# MCU.net
KiCad netlist of a schematic drawn in Altium Designer
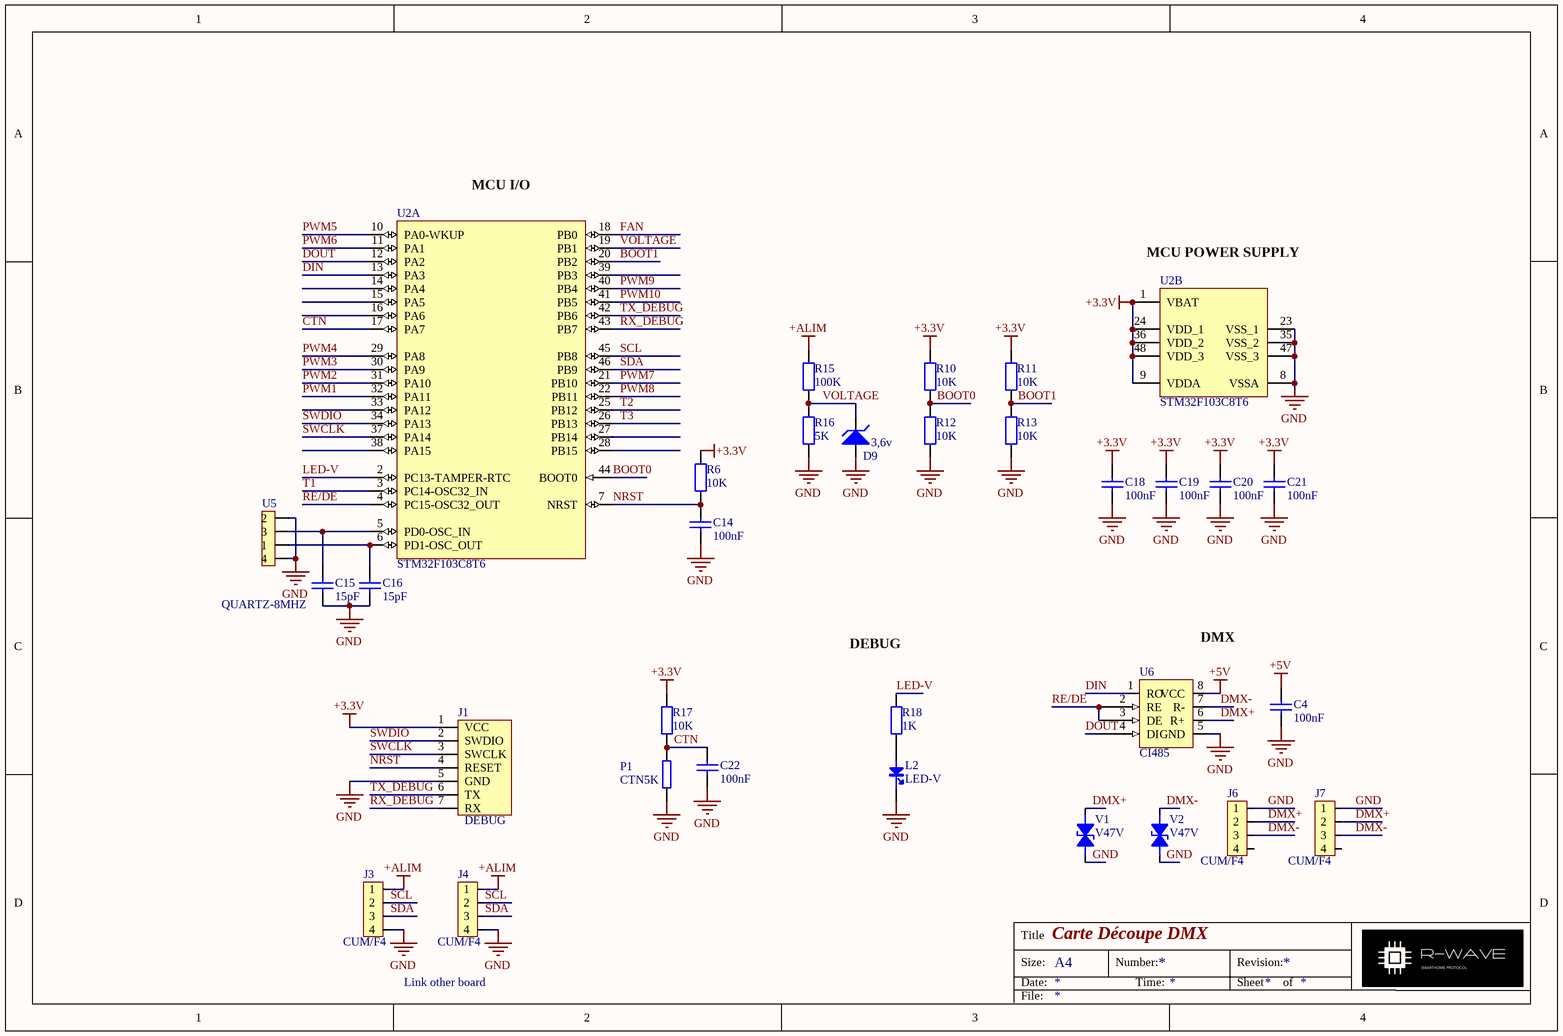
[diagram p0: MCU.SchDoc]

(export (version "E")
  (design (tool "Eeschema 10.0.6"))
  (components
    (comp (ref "C4")
      (value "100nF")
      (footprint "C0603")
      (description "Capacitor")
      (libsource (lib "MyLibrary") (part "Cap"))
    )
    (comp (ref "C14")
      (value "100nF")
      (footprint "C0603")
      (description "Capacitor")
      (libsource (lib "MyLibrary") (part "Cap"))
    )
    (comp (ref "C15")
      (value "15pF")
      (footprint "C0603")
      (description "Capacitor")
      (libsource (lib "MyLibrary") (part "Cap"))
    )
    (comp (ref "C16")
      (value "15pF")
      (footprint "C0603")
      (description "Capacitor")
      (libsource (lib "MyLibrary") (part "Cap"))
    )
    (comp (ref "C18")
      (value "100nF")
      (footprint "C0603")
      (description "Capacitor")
      (libsource (lib "MyLibrary") (part "Cap"))
    )
    (comp (ref "C19")
      (value "100nF")
      (footprint "C0603")
      (description "Capacitor")
      (libsource (lib "MyLibrary") (part "Cap"))
    )
    (comp (ref "C20")
      (value "100nF")
      (footprint "C0603")
      (description "Capacitor")
      (libsource (lib "MyLibrary") (part "Cap"))
    )
    (comp (ref "C21")
      (value "100nF")
      (footprint "C0603")
      (description "Capacitor")
      (libsource (lib "MyLibrary") (part "Cap"))
    )
    (comp (ref "C22")
      (value "100nF")
      (footprint "C0603")
      (description "Capacitor")
      (libsource (lib "MyLibrary") (part "Cap"))
    )
    (comp (ref "D9")
      (value "3,6v")
      (footprint "SOD123")
      (description "Zener Diode")
      (libsource (lib "MyLibrary") (part "D Zener"))
    )
    (comp (ref "J1")
      (value "~")
      (footprint "CON_PROG")
      (description "Programming Connector")
      (libsource (lib "MyLibrary") (part "CON-PROG"))
    )
    (comp (ref "J3")
      (value "CUM/F4")
      (footprint "CNT4F5")
      (description "connecteur  4 points")
      (libsource (lib "PROTEL") (part "CUM/F4"))
    )
    (comp (ref "J4")
      (value "CUM/F4")
      (footprint "CNT4F5")
      (description "connecteur  4 points")
      (libsource (lib "PROTEL") (part "CUM/F4"))
    )
    (comp (ref "J6")
      (value "CUM/F4")
      (footprint "CNT4S")
      (description "connecteur  4 points")
      (libsource (lib "PROTEL") (part "CUM/F4"))
    )
    (comp (ref "J7")
      (value "CUM/F4")
      (footprint "CNT4S")
      (description "connecteur  4 points")
      (libsource (lib "PROTEL") (part "CUM/F4"))
    )
    (comp (ref "L2")
      (value "LED-V")
      (footprint "LED-V1A")
      (description "LED  piquer  ou  CMS verte")
      (libsource (lib "PROTEL") (part "LED-V"))
    )
    (comp (ref "P1")
      (value "CTN5K")
      (footprint "DIV015")
      (description "Photoresistance")
      (libsource (lib "PROTEL") (part "CTN5K"))
    )
    (comp (ref "R6")
      (value "10K")
      (footprint "R0603")
      (description "Thin Metal Film Resistor")
      (libsource (lib "MyLibrary") (part "Res"))
    )
    (comp (ref "R10")
      (value "10K")
      (footprint "R0603")
      (description "Thin Metal Film Resistor")
      (libsource (lib "MyLibrary") (part "Res"))
    )
    (comp (ref "R11")
      (value "10K")
      (footprint "R0603")
      (description "Thin Metal Film Resistor")
      (libsource (lib "MyLibrary") (part "Res"))
    )
    (comp (ref "R12")
      (value "10K")
      (footprint "R0603")
      (description "Thin Metal Film Resistor")
      (libsource (lib "MyLibrary") (part "Res"))
    )
    (comp (ref "R13")
      (value "10K")
      (footprint "R0603")
      (description "Thin Metal Film Resistor")
      (libsource (lib "MyLibrary") (part "Res"))
    )
    (comp (ref "R15")
      (value "100K")
      (footprint "R0603")
      (description "Thin Metal Film Resistor")
      (libsource (lib "MyLibrary") (part "Res"))
    )
    (comp (ref "R16")
      (value "5K")
      (footprint "R0603")
      (description "Thin Metal Film Resistor")
      (libsource (lib "MyLibrary") (part "Res"))
    )
    (comp (ref "R17")
      (value "10K")
      (footprint "R0603")
      (description "Thin Metal Film Resistor")
      (libsource (lib "MyLibrary") (part "Res"))
    )
    (comp (ref "R18")
      (value "1K")
      (footprint "R0603")
      (description "Thin Metal Film Resistor")
      (libsource (lib "MyLibrary") (part "Res"))
    )
    (comp (ref "U2")
      (value "STM32F103C8T6")
      (footprint "TQFP-48")
      (libsource (lib "MyLibrary") (part "STM32F103C8T6"))
    )
    (comp (ref "U5")
      (value "QUARTZ-8MHZ")
      (footprint "QUA8G")
      (description "QUARTZ 8 MHZ CMS")
      (libsource (lib "PROTEL") (part "QUARTZ-8MHZ"))
    )
    (comp (ref "U6")
      (value "CI485")
      (footprint "CIA485A")
      (description "DRIVER  RS485")
      (libsource (lib "PROTEL") (part "CI485"))
    )
    (comp (ref "V1")
      (value "V47V")
      (footprint "VAR47A")
      (description "VARISTANCE 47V BOITIER 1206")
      (libsource (lib "PROTEL") (part "V47V"))
    )
    (comp (ref "V2")
      (value "V47V")
      (footprint "VAR47A")
      (description "VARISTANCE 47V BOITIER 1206")
      (libsource (lib "PROTEL") (part "V47V"))
    )
  )
  (nets
    (net (code "1") (name "+3.3V") (class "Default")
      (node (ref "C18") (pin "2") (pinfunction "2_2") (pintype "passive"))
      (node (ref "C19") (pin "2") (pinfunction "2_2") (pintype "passive"))
      (node (ref "C20") (pin "2") (pinfunction "2_2") (pintype "passive"))
      (node (ref "C21") (pin "2") (pinfunction "2_2") (pintype "passive"))
      (node (ref "J1") (pin "1") (pinfunction "VCC_1") (pintype "passive"))
      (node (ref "R10") (pin "2") (pinfunction "2_2") (pintype "passive"))
      (node (ref "R11") (pin "2") (pinfunction "2_2") (pintype "passive"))
      (node (ref "R17") (pin "2") (pinfunction "2_2") (pintype "passive"))
      (node (ref "R6") (pin "2") (pinfunction "2_2") (pintype "passive"))
      (node (ref "U2") (pin "1") (pinfunction "VBAT_1") (pintype "power_in"))
      (node (ref "U2") (pin "24") (pinfunction "VDD_1_24") (pintype "power_in"))
      (node (ref "U2") (pin "36") (pinfunction "VDD_2_36") (pintype "power_in"))
      (node (ref "U2") (pin "48") (pinfunction "VDD_3_48") (pintype "power_in"))
      (node (ref "U2") (pin "9") (pinfunction "VDDA_9") (pintype "power_in"))
    )
    (net (code "2") (name "+5V") (class "Default")
      (node (ref "C4") (pin "2") (pinfunction "2_2") (pintype "passive"))
      (node (ref "U6") (pin "8") (pinfunction "VCC_8") (pintype "power_in"))
    )
    (net (code "3") (name "+ALIM") (class "Default")
      (node (ref "J3") (pin "1") (pinfunction "1_1") (pintype "passive"))
      (node (ref "J4") (pin "1") (pinfunction "1_1") (pintype "passive"))
      (node (ref "R15") (pin "2") (pinfunction "2_2") (pintype "passive"))
    )
    (net (code "4") (name "/BOOT0") (class "Default")
      (node (ref "R10") (pin "1") (pinfunction "1_1") (pintype "passive"))
      (node (ref "R12") (pin "2") (pinfunction "2_2") (pintype "passive"))
      (node (ref "U2") (pin "44") (pinfunction "BOOT0_44") (pintype "input"))
    )
    (net (code "5") (name "/BOOT1") (class "Default")
      (node (ref "R11") (pin "1") (pinfunction "1_1") (pintype "passive"))
      (node (ref "R13") (pin "2") (pinfunction "2_2") (pintype "passive"))
      (node (ref "U2") (pin "20") (pinfunction "PB2_20") (pintype "bidirectional"))
    )
    (net (code "6") (name "/CTN") (class "Default")
      (node (ref "C22") (pin "2") (pinfunction "2_2") (pintype "passive"))
      (node (ref "P1") (pin "2") (pintype "passive"))
      (node (ref "R17") (pin "1") (pinfunction "1_1") (pintype "passive"))
      (node (ref "U2") (pin "17") (pinfunction "PA7_17") (pintype "bidirectional"))
    )
    (net (code "7") (name "/DIN") (class "Default")
      (node (ref "U2") (pin "13") (pinfunction "PA3_13") (pintype "bidirectional"))
      (node (ref "U6") (pin "1") (pinfunction "RO_1") (pintype "bidirectional"))
    )
    (net (code "8") (name "/DMX+") (class "Default")
      (node (ref "J6") (pin "2") (pinfunction "2_2") (pintype "passive"))
      (node (ref "J7") (pin "2") (pinfunction "2_2") (pintype "passive"))
      (node (ref "U6") (pin "6") (pinfunction "R+_6") (pintype "bidirectional"))
      (node (ref "V1") (pin "1") (pinfunction "1_1") (pintype "passive"))
    )
    (net (code "9") (name "/DMX-") (class "Default")
      (node (ref "J6") (pin "3") (pinfunction "3_3") (pintype "passive"))
      (node (ref "J7") (pin "3") (pinfunction "3_3") (pintype "passive"))
      (node (ref "U6") (pin "7") (pinfunction "R-_7") (pintype "bidirectional"))
      (node (ref "V2") (pin "1") (pinfunction "1_1") (pintype "passive"))
    )
    (net (code "10") (name "/DOUT") (class "Default")
      (node (ref "U2") (pin "12") (pinfunction "PA2_12") (pintype "bidirectional"))
      (node (ref "U6") (pin "4") (pinfunction "DI_4") (pintype "input"))
    )
    (net (code "11") (name "/FAN") (class "Default")
      (node (ref "U2") (pin "18") (pinfunction "PB0_18") (pintype "bidirectional"))
    )
    (net (code "12") (name "/LED-V") (class "Default")
      (node (ref "R18") (pin "2") (pinfunction "2_2") (pintype "passive"))
      (node (ref "U2") (pin "2") (pinfunction "PC13-TAMPER-RTC_2") (pintype "bidirectional"))
    )
    (net (code "13") (name "/NRST") (class "Default")
      (node (ref "C14") (pin "2") (pinfunction "2_2") (pintype "passive"))
      (node (ref "J1") (pin "4") (pinfunction "RESET_4") (pintype "passive"))
      (node (ref "R6") (pin "1") (pinfunction "1_1") (pintype "passive"))
      (node (ref "U2") (pin "7") (pinfunction "NRST_7") (pintype "bidirectional"))
    )
    (net (code "14") (name "/PWM1") (class "Default")
      (node (ref "U2") (pin "32") (pinfunction "PA11_32") (pintype "bidirectional"))
    )
    (net (code "15") (name "/PWM2") (class "Default")
      (node (ref "U2") (pin "31") (pinfunction "PA10_31") (pintype "bidirectional"))
    )
    (net (code "16") (name "/PWM3") (class "Default")
      (node (ref "U2") (pin "30") (pinfunction "PA9_30") (pintype "bidirectional"))
    )
    (net (code "17") (name "/PWM4") (class "Default")
      (node (ref "U2") (pin "29") (pinfunction "PA8_29") (pintype "bidirectional"))
    )
    (net (code "18") (name "/PWM5") (class "Default")
      (node (ref "U2") (pin "10") (pinfunction "PA0-WKUP_10") (pintype "bidirectional"))
    )
    (net (code "19") (name "/PWM6") (class "Default")
      (node (ref "U2") (pin "11") (pinfunction "PA1_11") (pintype "bidirectional"))
    )
    (net (code "20") (name "/PWM7") (class "Default")
      (node (ref "U2") (pin "21") (pinfunction "PB10_21") (pintype "bidirectional"))
    )
    (net (code "21") (name "/PWM8") (class "Default")
      (node (ref "U2") (pin "22") (pinfunction "PB11_22") (pintype "bidirectional"))
    )
    (net (code "22") (name "/PWM9") (class "Default")
      (node (ref "U2") (pin "40") (pinfunction "PB4_40") (pintype "bidirectional"))
    )
    (net (code "23") (name "/PWM10") (class "Default")
      (node (ref "U2") (pin "41") (pinfunction "PB5_41") (pintype "bidirectional"))
    )
    (net (code "24") (name "/RE{slash}DE") (class "Default")
      (node (ref "U2") (pin "4") (pinfunction "PC15-OSC32_OUT_4") (pintype "bidirectional"))
      (node (ref "U6") (pin "2") (pinfunction "RE_2") (pintype "input"))
      (node (ref "U6") (pin "3") (pinfunction "DE_3") (pintype "input"))
    )
    (net (code "25") (name "/RX_DEBUG") (class "Default")
      (node (ref "J1") (pin "7") (pinfunction "RX_7") (pintype "passive"))
      (node (ref "U2") (pin "43") (pinfunction "PB7_43") (pintype "bidirectional"))
    )
    (net (code "26") (name "/SCL") (class "Default")
      (node (ref "J3") (pin "2") (pinfunction "2_2") (pintype "passive"))
      (node (ref "J4") (pin "2") (pinfunction "2_2") (pintype "passive"))
      (node (ref "U2") (pin "45") (pinfunction "PB8_45") (pintype "bidirectional"))
    )
    (net (code "27") (name "/SDA") (class "Default")
      (node (ref "J3") (pin "3") (pinfunction "3_3") (pintype "passive"))
      (node (ref "J4") (pin "3") (pinfunction "3_3") (pintype "passive"))
      (node (ref "U2") (pin "46") (pinfunction "PB9_46") (pintype "bidirectional"))
    )
    (net (code "28") (name "/SWCLK") (class "Default")
      (node (ref "J1") (pin "3") (pinfunction "SWCLK_3") (pintype "passive"))
      (node (ref "U2") (pin "37") (pinfunction "PA14_37") (pintype "bidirectional"))
    )
    (net (code "29") (name "/SWDIO") (class "Default")
      (node (ref "J1") (pin "2") (pinfunction "SWDIO_2") (pintype "passive"))
      (node (ref "U2") (pin "34") (pinfunction "PA13_34") (pintype "bidirectional"))
    )
    (net (code "30") (name "/T1") (class "Default")
      (node (ref "U2") (pin "3") (pinfunction "PC14-OSC32_IN_3") (pintype "bidirectional"))
    )
    (net (code "31") (name "/T2") (class "Default")
      (node (ref "U2") (pin "25") (pinfunction "PB12_25") (pintype "bidirectional"))
    )
    (net (code "32") (name "/T3") (class "Default")
      (node (ref "U2") (pin "26") (pinfunction "PB13_26") (pintype "bidirectional"))
    )
    (net (code "33") (name "/TX_DEBUG") (class "Default")
      (node (ref "J1") (pin "6") (pinfunction "TX_6") (pintype "passive"))
      (node (ref "U2") (pin "42") (pinfunction "PB6_42") (pintype "bidirectional"))
    )
    (net (code "34") (name "/VOLTAGE") (class "Default")
      (node (ref "D9") (pin "2") (pinfunction "K_2") (pintype "passive"))
      (node (ref "R15") (pin "1") (pinfunction "1_1") (pintype "passive"))
      (node (ref "R16") (pin "2") (pinfunction "2_2") (pintype "passive"))
      (node (ref "U2") (pin "19") (pinfunction "PB1_19") (pintype "bidirectional"))
    )
    (net (code "35") (name "GND") (class "Default")
      (node (ref "C14") (pin "1") (pinfunction "1_1") (pintype "passive"))
      (node (ref "C15") (pin "2") (pinfunction "2_2") (pintype "passive"))
      (node (ref "C16") (pin "1") (pinfunction "1_1") (pintype "passive"))
      (node (ref "C18") (pin "1") (pinfunction "1_1") (pintype "passive"))
      (node (ref "C19") (pin "1") (pinfunction "1_1") (pintype "passive"))
      (node (ref "C20") (pin "1") (pinfunction "1_1") (pintype "passive"))
      (node (ref "C21") (pin "1") (pinfunction "1_1") (pintype "passive"))
      (node (ref "C22") (pin "1") (pinfunction "1_1") (pintype "passive"))
      (node (ref "C4") (pin "1") (pinfunction "1_1") (pintype "passive"))
      (node (ref "D9") (pin "1") (pinfunction "A_1") (pintype "passive"))
      (node (ref "J1") (pin "5") (pinfunction "GND_5") (pintype "passive"))
      (node (ref "J3") (pin "4") (pinfunction "4_4") (pintype "passive"))
      (node (ref "J4") (pin "4") (pinfunction "4_4") (pintype "passive"))
      (node (ref "J6") (pin "1") (pinfunction "1_1") (pintype "passive"))
      (node (ref "J7") (pin "1") (pinfunction "1_1") (pintype "passive"))
      (node (ref "L2") (pin "2") (pintype "passive"))
      (node (ref "P1") (pin "1") (pintype "passive"))
      (node (ref "R12") (pin "1") (pinfunction "1_1") (pintype "passive"))
      (node (ref "R13") (pin "1") (pinfunction "1_1") (pintype "passive"))
      (node (ref "R16") (pin "1") (pinfunction "1_1") (pintype "passive"))
      (node (ref "U2") (pin "23") (pinfunction "VSS_1_23") (pintype "power_in"))
      (node (ref "U2") (pin "35") (pinfunction "VSS_2_35") (pintype "power_in"))
      (node (ref "U2") (pin "47") (pinfunction "VSS_3_47") (pintype "power_in"))
      (node (ref "U2") (pin "8") (pinfunction "VSSA_8") (pintype "power_in"))
      (node (ref "U5") (pin "2") (pinfunction "2_2") (pintype "passive"))
      (node (ref "U5") (pin "4") (pinfunction "4_4") (pintype "passive"))
      (node (ref "U6") (pin "5") (pinfunction "GND_5") (pintype "power_in"))
      (node (ref "V1") (pin "2") (pinfunction "2_2") (pintype "passive"))
      (node (ref "V2") (pin "2") (pinfunction "2_2") (pintype "passive"))
    )
    (net (code "36") (name "Net-(L2-Pad1)") (class "Default")
      (node (ref "L2") (pin "1") (pintype "passive"))
      (node (ref "R18") (pin "1") (pinfunction "1_1") (pintype "passive"))
    )
    (net (code "37") (name "Net-(U2A-PD0-OSC_IN)") (class "Default")
      (node (ref "C15") (pin "1") (pinfunction "1_1") (pintype "passive"))
      (node (ref "U2") (pin "5") (pinfunction "PD0-OSC_IN_5") (pintype "bidirectional"))
      (node (ref "U5") (pin "3") (pinfunction "3_3") (pintype "passive"))
    )
    (net (code "38") (name "Net-(U2A-PD1-OSC_OUT)") (class "Default")
      (node (ref "C16") (pin "2") (pinfunction "2_2") (pintype "passive"))
      (node (ref "U2") (pin "6") (pinfunction "PD1-OSC_OUT_6") (pintype "bidirectional"))
      (node (ref "U5") (pin "1") (pinfunction "1_1") (pintype "passive"))
    )
    (net (code "39") (name "unconnected-(J6-Pad4)") (class "Default")
      (node (ref "J6") (pin "4") (pinfunction "4_4") (pintype "passive"))
    )
    (net (code "40") (name "unconnected-(J7-Pad4)") (class "Default")
      (node (ref "J7") (pin "4") (pinfunction "4_4") (pintype "passive"))
    )
    (net (code "41") (name "unconnected-(U2A-PA4-Pad14)") (class "Default")
      (node (ref "U2") (pin "14") (pinfunction "PA4_14") (pintype "bidirectional"))
    )
    (net (code "42") (name "unconnected-(U2A-PA5-Pad15)") (class "Default")
      (node (ref "U2") (pin "15") (pinfunction "PA5_15") (pintype "bidirectional"))
    )
    (net (code "43") (name "unconnected-(U2A-PA6-Pad16)") (class "Default")
      (node (ref "U2") (pin "16") (pinfunction "PA6_16") (pintype "bidirectional"))
    )
    (net (code "44") (name "unconnected-(U2A-PA12-Pad33)") (class "Default")
      (node (ref "U2") (pin "33") (pinfunction "PA12_33") (pintype "bidirectional"))
    )
    (net (code "45") (name "unconnected-(U2A-PA15-Pad38)") (class "Default")
      (node (ref "U2") (pin "38") (pinfunction "PA15_38") (pintype "bidirectional"))
    )
    (net (code "46") (name "unconnected-(U2A-PB3-Pad39)") (class "Default")
      (node (ref "U2") (pin "39") (pinfunction "PB3_39") (pintype "bidirectional"))
    )
    (net (code "47") (name "unconnected-(U2A-PB14-Pad27)") (class "Default")
      (node (ref "U2") (pin "27") (pinfunction "PB14_27") (pintype "bidirectional"))
    )
    (net (code "48") (name "unconnected-(U2A-PB15-Pad28)") (class "Default")
      (node (ref "U2") (pin "28") (pinfunction "PB15_28") (pintype "bidirectional"))
    )
  )
)
